# DACEWAVE.net
KiCad netlist of a schematic drawn in Altium Designer
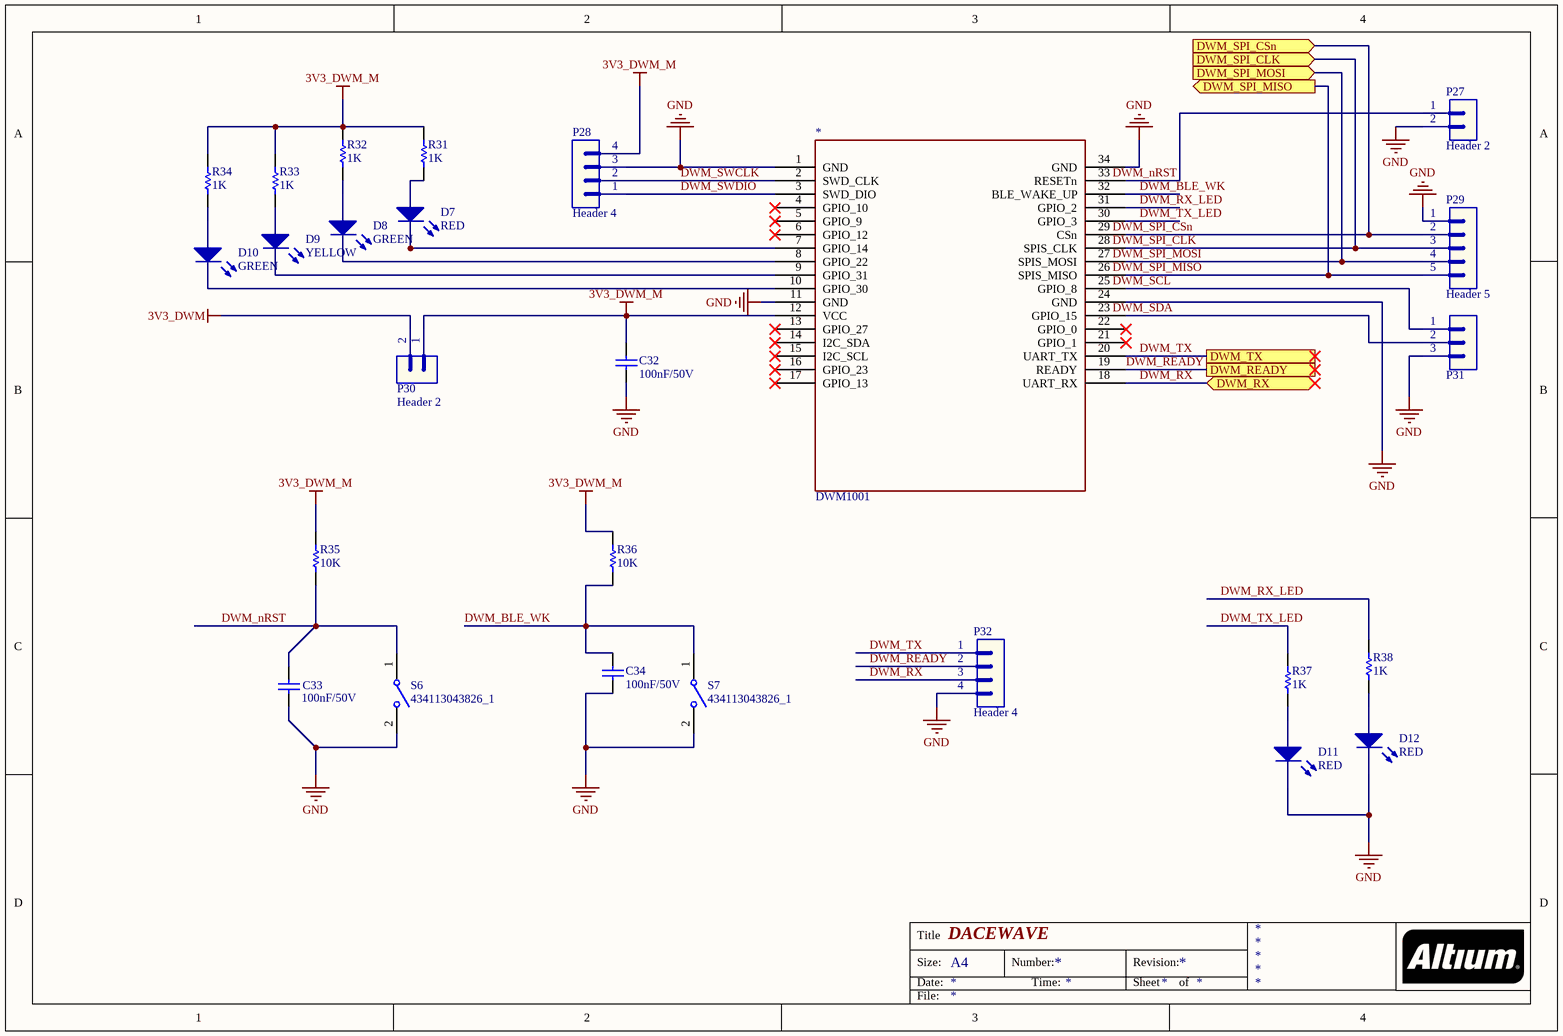
[diagram p0: DACEWAVE.SchDoc]

(export (version "E")
  (design (tool "Eeschema 10.0.6"))
  (components
    (comp (ref "*") (value "DWM1001") (footprint "DWM1001") (libsource (lib "PIF_ROBOT") (part "DWM1001")))
    (comp (ref "C32")
      (value "100nF/50V")
      (footprint "CAP-SM-0805")
      (description "CAP CER 0.1UF 50V Y5V 0805")
      (fields
        (field (name "MANUFACTURER") "Samsung Electro-Mechanics")
        (field (name "MANUFACTURER PART NUMBER") "CL21F104ZBCNNNC")
      )
      (libsource (lib "PIF_ROBOT") (part "Cap-100nF-50V-0805"))
    )
    (comp (ref "C33")
      (value "100nF/50V")
      (footprint "CAP-SM-0805")
      (description "CAP CER 0.1UF 50V Y5V 0805")
      (fields
        (field (name "MANUFACTURER") "Samsung Electro-Mechanics")
        (field (name "MANUFACTURER PART NUMBER") "CL21F104ZBCNNNC")
      )
      (libsource (lib "PIF_ROBOT") (part "Cap-100nF-50V-0805"))
    )
    (comp (ref "C34")
      (value "100nF/50V")
      (footprint "CAP-SM-0805")
      (description "CAP CER 0.1UF 50V Y5V 0805")
      (fields
        (field (name "MANUFACTURER") "Samsung Electro-Mechanics")
        (field (name "MANUFACTURER PART NUMBER") "CL21F104ZBCNNNC")
      )
      (libsource (lib "PIF_ROBOT") (part "Cap-100nF-50V-0805"))
    )
    (comp (ref "D7") (value "RED") (footprint "LED_0805_Blue") (libsource (lib "PIF_C16_lib") (part "LED")))
    (comp (ref "D8") (value "GREEN") (footprint "LED_0805_Blue") (libsource (lib "PIF_C16_lib") (part "LED")))
    (comp (ref "D9")
      (value "YELLOW")
      (footprint "LED_0805_Blue")
      (libsource (lib "PIF_C16_lib") (part "LED"))
    )
    (comp (ref "D10")
      (value "GREEN")
      (footprint "LED_0805_Blue")
      (libsource (lib "PIF_C16_lib") (part "LED"))
    )
    (comp (ref "D11") (value "RED") (footprint "LED_0805_Blue") (libsource (lib "PIF_C16_lib") (part "LED")))
    (comp (ref "D12") (value "RED") (footprint "LED_0805_Blue") (libsource (lib "PIF_C16_lib") (part "LED")))
    (comp (ref "P27")
      (value "Header 2")
      (footprint "JP2")
      (description "Header, 2-Pin")
      (fields (field (name "PUBLISHER") "Altium Limited"))
      (libsource (lib "") (part "Header 2_1"))
    )
    (comp (ref "P28")
      (value "Header 4")
      (footprint "JP4")
      (description "Header, 4-Pin")
      (fields (field (name "PUBLISHER") "Altium Limited"))
      (libsource (lib "") (part "Header 4_1"))
    )
    (comp (ref "P29")
      (value "Header 5")
      (footprint "JP5")
      (description "Header, 5-Pin")
      (fields (field (name "PUBLISHER") "Altium Limited"))
      (libsource (lib "PIF_ROBOT") (part "Header 5"))
    )
    (comp (ref "P30")
      (value "Header 2")
      (footprint "JP2")
      (description "Header, 2-Pin")
      (fields (field (name "PUBLISHER") "Altium Limited"))
      (libsource (lib "PIF_ROBOT") (part "Header 2"))
    )
    (comp (ref "P31")
      (value "Header 3")
      (footprint "JP3")
      (description "Header, 3-Pin")
      (fields (field (name "PUBLISHER") "Altium Limited"))
      (libsource (lib "PIF_ROBOT") (part "Header 3"))
    )
    (comp (ref "P32")
      (value "Header 4")
      (footprint "JP4")
      (description "Header, 4-Pin")
      (fields (field (name "PUBLISHER") "Altium Limited"))
      (libsource (lib "PIF_ROBOT") (part "Header 4"))
    )
    (comp (ref "R31")
      (value "1K")
      (footprint "RES-SM-0805")
      (description "RES 0 OHM JUMPER 0805")
      (fields
        (field (name "MANUFACTURER") "Vishay Dale")
        (field (name "MANUFACTURER PART NUMBER") "WSL080500000ZEA9")
      )
      (libsource (lib "PIF_ROBOT") (part "Res-0-0805"))
    )
    (comp (ref "R32")
      (value "1K")
      (footprint "RES-SM-0805")
      (description "RES 0 OHM JUMPER 0805")
      (fields
        (field (name "MANUFACTURER") "Vishay Dale")
        (field (name "MANUFACTURER PART NUMBER") "WSL080500000ZEA9")
      )
      (libsource (lib "PIF_ROBOT") (part "Res-0-0805"))
    )
    (comp (ref "R33")
      (value "1K")
      (footprint "RES-SM-0805")
      (description "RES 0 OHM JUMPER 0805")
      (fields
        (field (name "MANUFACTURER") "Vishay Dale")
        (field (name "MANUFACTURER PART NUMBER") "WSL080500000ZEA9")
      )
      (libsource (lib "PIF_ROBOT") (part "Res-0-0805"))
    )
    (comp (ref "R34")
      (value "1K")
      (footprint "RES-SM-0805")
      (description "RES 0 OHM JUMPER 0805")
      (fields
        (field (name "MANUFACTURER") "Vishay Dale")
        (field (name "MANUFACTURER PART NUMBER") "WSL080500000ZEA9")
      )
      (libsource (lib "PIF_ROBOT") (part "Res-0-0805"))
    )
    (comp (ref "R35")
      (value "10K")
      (footprint "RES-SM-0805")
      (description "RES 0 OHM JUMPER 0805")
      (fields
        (field (name "MANUFACTURER") "Vishay Dale")
        (field (name "MANUFACTURER PART NUMBER") "WSL080500000ZEA9")
      )
      (libsource (lib "PIF_ROBOT") (part "Res-0-0805"))
    )
    (comp (ref "R36")
      (value "10K")
      (footprint "RES-SM-0805")
      (description "RES 0 OHM JUMPER 0805")
      (fields
        (field (name "MANUFACTURER") "Vishay Dale")
        (field (name "MANUFACTURER PART NUMBER") "WSL080500000ZEA9")
      )
      (libsource (lib "PIF_ROBOT") (part "Res-0-0805"))
    )
    (comp (ref "R37")
      (value "1K")
      (footprint "RES-SM-0805")
      (description "RES 0 OHM JUMPER 0805")
      (fields
        (field (name "MANUFACTURER") "Vishay Dale")
        (field (name "MANUFACTURER PART NUMBER") "WSL080500000ZEA9")
      )
      (libsource (lib "PIF_ROBOT") (part "Res-0-0805"))
    )
    (comp (ref "R38")
      (value "1K")
      (footprint "RES-SM-0805")
      (description "RES 0 OHM JUMPER 0805")
      (fields
        (field (name "MANUFACTURER") "Vishay Dale")
        (field (name "MANUFACTURER PART NUMBER") "WSL080500000ZEA9")
      )
      (libsource (lib "PIF_ROBOT") (part "Res-0-0805"))
    )
    (comp (ref "S6")
      (value "434113043826_1")
      (footprint "434113043826")
      (description "WS-TASV J-Bend SMT Tact Switch 6x3.5mm, height 4.3mm, 260gf")
      (fields (field (name "PART NUMBER") "434113043826") (field (name "PUBLISHER") "Wurth Elektronik"))
      (libsource (lib "PIF_ROBOT") (part "434113043826_1"))
    )
    (comp (ref "S7")
      (value "434113043826_1")
      (footprint "434113043826")
      (description "WS-TASV J-Bend SMT Tact Switch 6x3.5mm, height 4.3mm, 260gf")
      (fields (field (name "PART NUMBER") "434113043826") (field (name "PUBLISHER") "Wurth Elektronik"))
      (libsource (lib "PIF_ROBOT") (part "434113043826_1"))
    )
  )
  (nets
    (net (code "1") (name "/DWM_BLE_WK") (class "Default")
      (node (ref "*") (pin "32") (pinfunction "BLE_WAKE_UP_32") (pintype "passive"))
      (node (ref "C34") (pin "1") (pinfunction "1_1") (pintype "passive"))
      (node (ref "R36") (pin "1") (pinfunction "1_1") (pintype "passive"))
      (node (ref "S7") (pin "1") (pinfunction "1_1") (pintype "passive"))
    )
    (net (code "2") (name "/DWM_READY") (class "Default")
      (node (ref "*") (pin "19") (pinfunction "READY_19") (pintype "passive"))
      (node (ref "P32") (pin "2") (pinfunction "2_2") (pintype "passive"))
    )
    (net (code "3") (name "/DWM_RX") (class "Default")
      (node (ref "*") (pin "18") (pinfunction "UART_RX_18") (pintype "passive"))
      (node (ref "P32") (pin "3") (pinfunction "3_3") (pintype "passive"))
    )
    (net (code "4") (name "/DWM_RX_LED") (class "Default")
      (node (ref "*") (pin "31") (pinfunction "GPIO_2_31") (pintype "passive"))
      (node (ref "R38") (pin "2") (pinfunction "2_2") (pintype "passive"))
    )
    (net (code "7") (name "/DWM_SPI_CLK") (class "Default")
      (node (ref "*") (pin "28") (pinfunction "SPIS_CLK_28") (pintype "passive"))
      (node (ref "P29") (pin "3") (pinfunction "3_3") (pintype "passive"))
    )
    (net (code "8") (name "/DWM_SPI_CSn") (class "Default")
      (node (ref "*") (pin "29") (pinfunction "CSn_29") (pintype "passive"))
      (node (ref "P29") (pin "2") (pinfunction "2_2") (pintype "passive"))
    )
    (net (code "9") (name "/DWM_SPI_MISO") (class "Default")
      (node (ref "*") (pin "26") (pinfunction "SPIS_MISO_26") (pintype "passive"))
      (node (ref "P29") (pin "5") (pinfunction "5_5") (pintype "passive"))
    )
    (net (code "10") (name "/DWM_SPI_MOSI") (class "Default")
      (node (ref "*") (pin "27") (pinfunction "SPIS_MOSI_27") (pintype "passive"))
      (node (ref "P29") (pin "4") (pinfunction "4_4") (pintype "passive"))
    )
    (net (code "11") (name "/DWM_SWCLK") (class "Default")
      (node (ref "*") (pin "2") (pinfunction "SWD_CLK_2") (pintype "passive"))
      (node (ref "P28") (pin "2") (pinfunction "2_2") (pintype "passive"))
    )
    (net (code "12") (name "/DWM_SWDIO") (class "Default")
      (node (ref "*") (pin "3") (pinfunction "SWD_DIO_3") (pintype "passive"))
      (node (ref "P28") (pin "1") (pinfunction "1_1") (pintype "passive"))
    )
    (net (code "13") (name "/DWM_TX") (class "Default")
      (node (ref "*") (pin "20") (pinfunction "UART_TX_20") (pintype "passive"))
      (node (ref "P32") (pin "1") (pinfunction "1_1") (pintype "passive"))
    )
    (net (code "14") (name "/DWM_TX_LED") (class "Default")
      (node (ref "*") (pin "30") (pinfunction "GPIO_3_30") (pintype "passive"))
      (node (ref "R37") (pin "2") (pinfunction "2_2") (pintype "passive"))
    )
    (net (code "15") (name "/DWM_nRST") (class "Default")
      (node (ref "C33") (pin "1") (pinfunction "1_1") (pintype "passive"))
      (node (ref "R35") (pin "1") (pinfunction "1_1") (pintype "passive"))
      (node (ref "S6") (pin "1") (pinfunction "1_1") (pintype "passive"))
    )
    (net (code "16") (name "3V3_DWM") (class "Default")
      (node (ref "P30") (pin "2") (pinfunction "2_2") (pintype "passive"))
    )
    (net (code "17") (name "3V3_DWM_M") (class "Default")
      (node (ref "*") (pin "12") (pinfunction "VCC_12") (pintype "passive"))
      (node (ref "C32") (pin "1") (pinfunction "1_1") (pintype "passive"))
      (node (ref "P28") (pin "4") (pinfunction "4_4") (pintype "passive"))
      (node (ref "P30") (pin "1") (pinfunction "1_1") (pintype "passive"))
      (node (ref "R31") (pin "2") (pinfunction "2_2") (pintype "passive"))
      (node (ref "R32") (pin "2") (pinfunction "2_2") (pintype "passive"))
      (node (ref "R33") (pin "2") (pinfunction "2_2") (pintype "passive"))
      (node (ref "R34") (pin "2") (pinfunction "2_2") (pintype "passive"))
      (node (ref "R35") (pin "2") (pinfunction "2_2") (pintype "passive"))
      (node (ref "R36") (pin "2") (pinfunction "2_2") (pintype "passive"))
    )
    (net (code "18") (name "GND") (class "Default")
      (node (ref "*") (pin "1") (pinfunction "GND_1") (pintype "passive"))
      (node (ref "*") (pin "11") (pinfunction "GND_11") (pintype "passive"))
      (node (ref "*") (pin "24") (pinfunction "GND_24") (pintype "passive"))
      (node (ref "*") (pin "34") (pinfunction "GND_34") (pintype "passive"))
      (node (ref "C32") (pin "2") (pinfunction "2_2") (pintype "passive"))
      (node (ref "C33") (pin "2") (pinfunction "2_2") (pintype "passive"))
      (node (ref "C34") (pin "2") (pinfunction "2_2") (pintype "passive"))
      (node (ref "D11") (pin "2") (pinfunction "K_2") (pintype "passive"))
      (node (ref "D12") (pin "2") (pinfunction "K_2") (pintype "passive"))
      (node (ref "P27") (pin "2") (pinfunction "2_2") (pintype "passive"))
      (node (ref "P28") (pin "3") (pinfunction "3_3") (pintype "passive"))
      (node (ref "P29") (pin "1") (pinfunction "1_1") (pintype "passive"))
      (node (ref "P31") (pin "3") (pinfunction "3_3") (pintype "passive"))
      (node (ref "P32") (pin "4") (pinfunction "4_4") (pintype "passive"))
      (node (ref "S6") (pin "2") (pinfunction "2_2") (pintype "passive"))
      (node (ref "S7") (pin "2") (pinfunction "2_2") (pintype "passive"))
    )
    (net (code "19") (name "Net-(*-GPIO_8)") (class "Default")
      (node (ref "*") (pin "25") (pinfunction "GPIO_8_25") (pintype "passive"))
      (node (ref "P31") (pin "1") (pinfunction "1_1") (pintype "passive"))
    )
    (net (code "20") (name "Net-(*-GPIO_14)") (class "Default")
      (node (ref "*") (pin "7") (pinfunction "GPIO_14_7") (pintype "passive"))
      (node (ref "D7") (pin "2") (pinfunction "K_2") (pintype "passive"))
    )
    (net (code "21") (name "Net-(*-GPIO_15)") (class "Default")
      (node (ref "*") (pin "23") (pinfunction "GPIO_15_23") (pintype "passive"))
      (node (ref "P31") (pin "2") (pinfunction "2_2") (pintype "passive"))
    )
    (net (code "22") (name "Net-(*-GPIO_22)") (class "Default")
      (node (ref "*") (pin "8") (pinfunction "GPIO_22_8") (pintype "passive"))
      (node (ref "D8") (pin "2") (pinfunction "K_2") (pintype "passive"))
    )
    (net (code "23") (name "Net-(*-GPIO_30)") (class "Default")
      (node (ref "*") (pin "10") (pinfunction "GPIO_30_10") (pintype "passive"))
      (node (ref "D10") (pin "2") (pinfunction "K_2") (pintype "passive"))
    )
    (net (code "24") (name "Net-(*-GPIO_31)") (class "Default")
      (node (ref "*") (pin "9") (pinfunction "GPIO_31_9") (pintype "passive"))
      (node (ref "D9") (pin "2") (pinfunction "K_2") (pintype "passive"))
    )
    (net (code "25") (name "Net-(*-RESETn)") (class "Default")
      (node (ref "*") (pin "33") (pinfunction "RESETn_33") (pintype "passive"))
      (node (ref "P27") (pin "1") (pinfunction "1_1") (pintype "passive"))
    )
    (net (code "26") (name "Net-(D7-A)") (class "Default")
      (node (ref "D7") (pin "1") (pinfunction "A_1") (pintype "passive"))
      (node (ref "R31") (pin "1") (pinfunction "1_1") (pintype "passive"))
    )
    (net (code "27") (name "Net-(D8-A)") (class "Default")
      (node (ref "D8") (pin "1") (pinfunction "A_1") (pintype "passive"))
      (node (ref "R32") (pin "1") (pinfunction "1_1") (pintype "passive"))
    )
    (net (code "28") (name "Net-(D9-A)") (class "Default")
      (node (ref "D9") (pin "1") (pinfunction "A_1") (pintype "passive"))
      (node (ref "R33") (pin "1") (pinfunction "1_1") (pintype "passive"))
    )
    (net (code "29") (name "Net-(D10-A)") (class "Default")
      (node (ref "D10") (pin "1") (pinfunction "A_1") (pintype "passive"))
      (node (ref "R34") (pin "1") (pinfunction "1_1") (pintype "passive"))
    )
    (net (code "30") (name "Net-(D11-A)") (class "Default")
      (node (ref "D11") (pin "1") (pinfunction "A_1") (pintype "passive"))
      (node (ref "R37") (pin "1") (pinfunction "1_1") (pintype "passive"))
    )
    (net (code "31") (name "Net-(D12-A)") (class "Default")
      (node (ref "D12") (pin "1") (pinfunction "A_1") (pintype "passive"))
      (node (ref "R38") (pin "1") (pinfunction "1_1") (pintype "passive"))
    )
    (net (code "32") (name "unconnected-(*-GPIO_0-Pad22)") (class "Default")
      (node (ref "*") (pin "22") (pinfunction "GPIO_0_22") (pintype "passive+no_connect"))
    )
    (net (code "33") (name "unconnected-(*-GPIO_1-Pad21)") (class "Default")
      (node (ref "*") (pin "21") (pinfunction "GPIO_1_21") (pintype "passive+no_connect"))
    )
    (net (code "34") (name "unconnected-(*-GPIO_9-Pad5)") (class "Default")
      (node (ref "*") (pin "5") (pinfunction "GPIO_9_5") (pintype "passive+no_connect"))
    )
    (net (code "35") (name "unconnected-(*-GPIO_10-Pad4)") (class "Default")
      (node (ref "*") (pin "4") (pinfunction "GPIO_10_4") (pintype "passive+no_connect"))
    )
    (net (code "36") (name "unconnected-(*-GPIO_12-Pad6)") (class "Default")
      (node (ref "*") (pin "6") (pinfunction "GPIO_12_6") (pintype "passive+no_connect"))
    )
    (net (code "37") (name "unconnected-(*-GPIO_13-Pad17)") (class "Default")
      (node (ref "*") (pin "17") (pinfunction "GPIO_13_17") (pintype "passive+no_connect"))
    )
    (net (code "38") (name "unconnected-(*-GPIO_23-Pad16)") (class "Default")
      (node (ref "*") (pin "16") (pinfunction "GPIO_23_16") (pintype "passive+no_connect"))
    )
    (net (code "39") (name "unconnected-(*-GPIO_27-Pad13)") (class "Default")
      (node (ref "*") (pin "13") (pinfunction "GPIO_27_13") (pintype "passive+no_connect"))
    )
    (net (code "40") (name "unconnected-(*-I2C_SCL-Pad15)") (class "Default")
      (node (ref "*") (pin "15") (pinfunction "I2C_SCL_15") (pintype "passive+no_connect"))
    )
    (net (code "41") (name "unconnected-(*-I2C_SDA-Pad14)") (class "Default")
      (node (ref "*") (pin "14") (pinfunction "I2C_SDA_14") (pintype "passive+no_connect"))
    )
  )
)
